# SHIELD_003.net
KiCad netlist of a schematic drawn in EAGLE
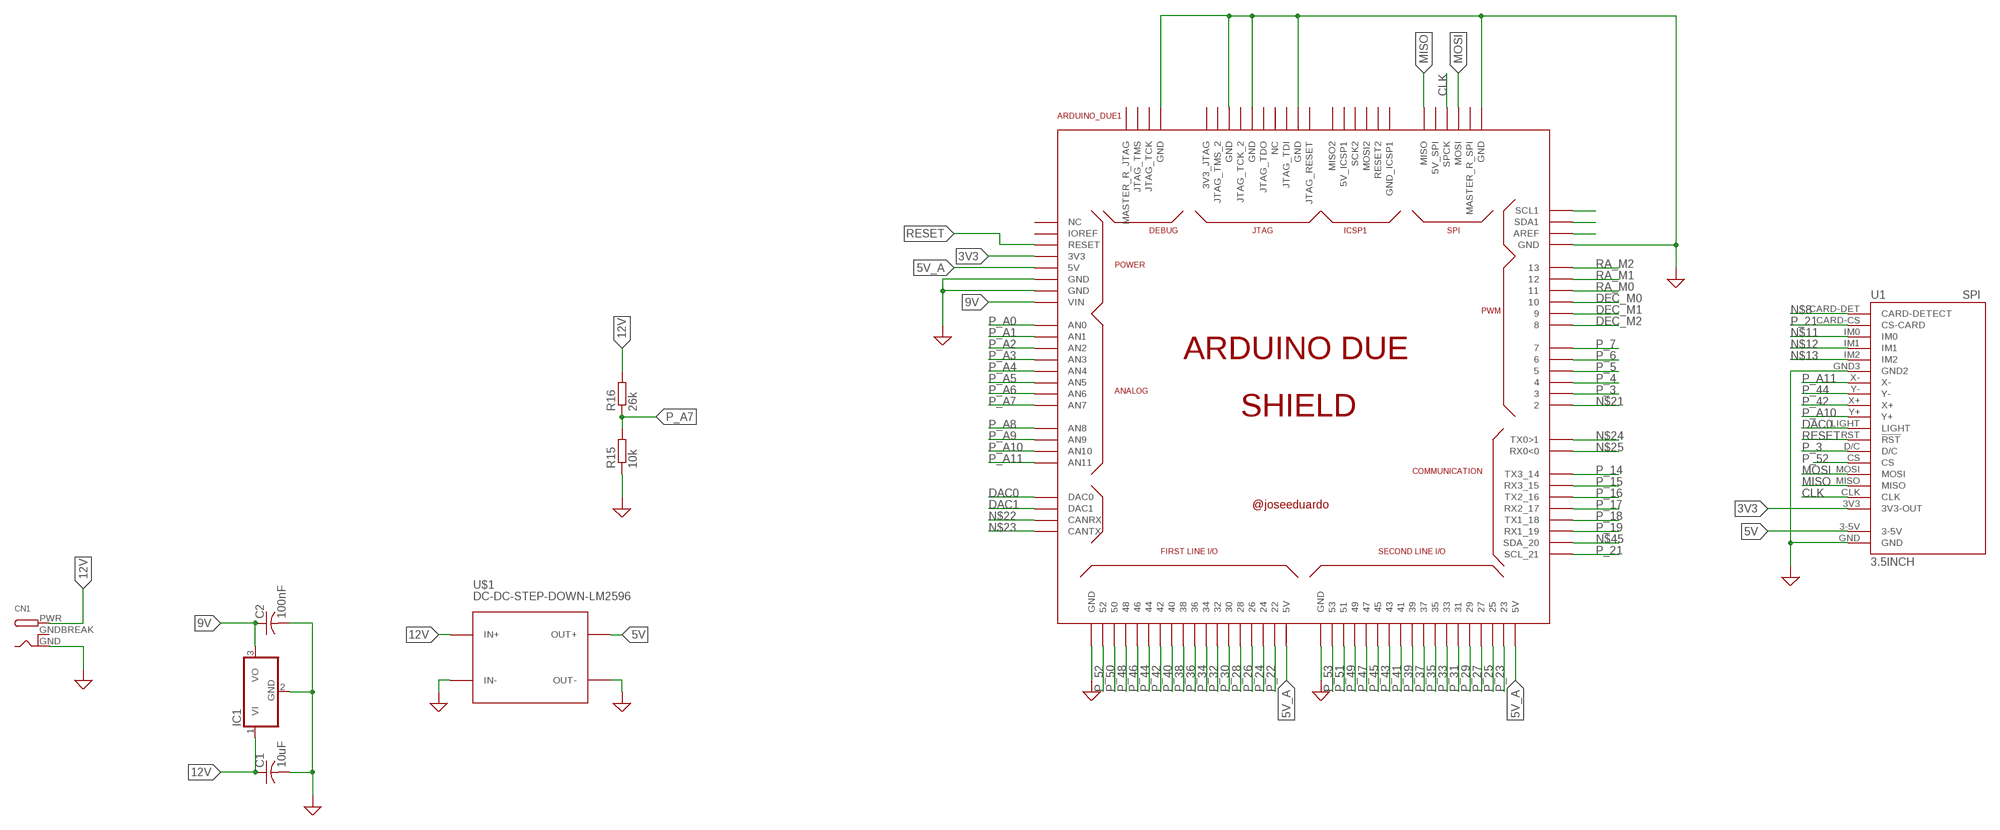
[diagram p0: schematic, sheet 1, part 1 of 3]
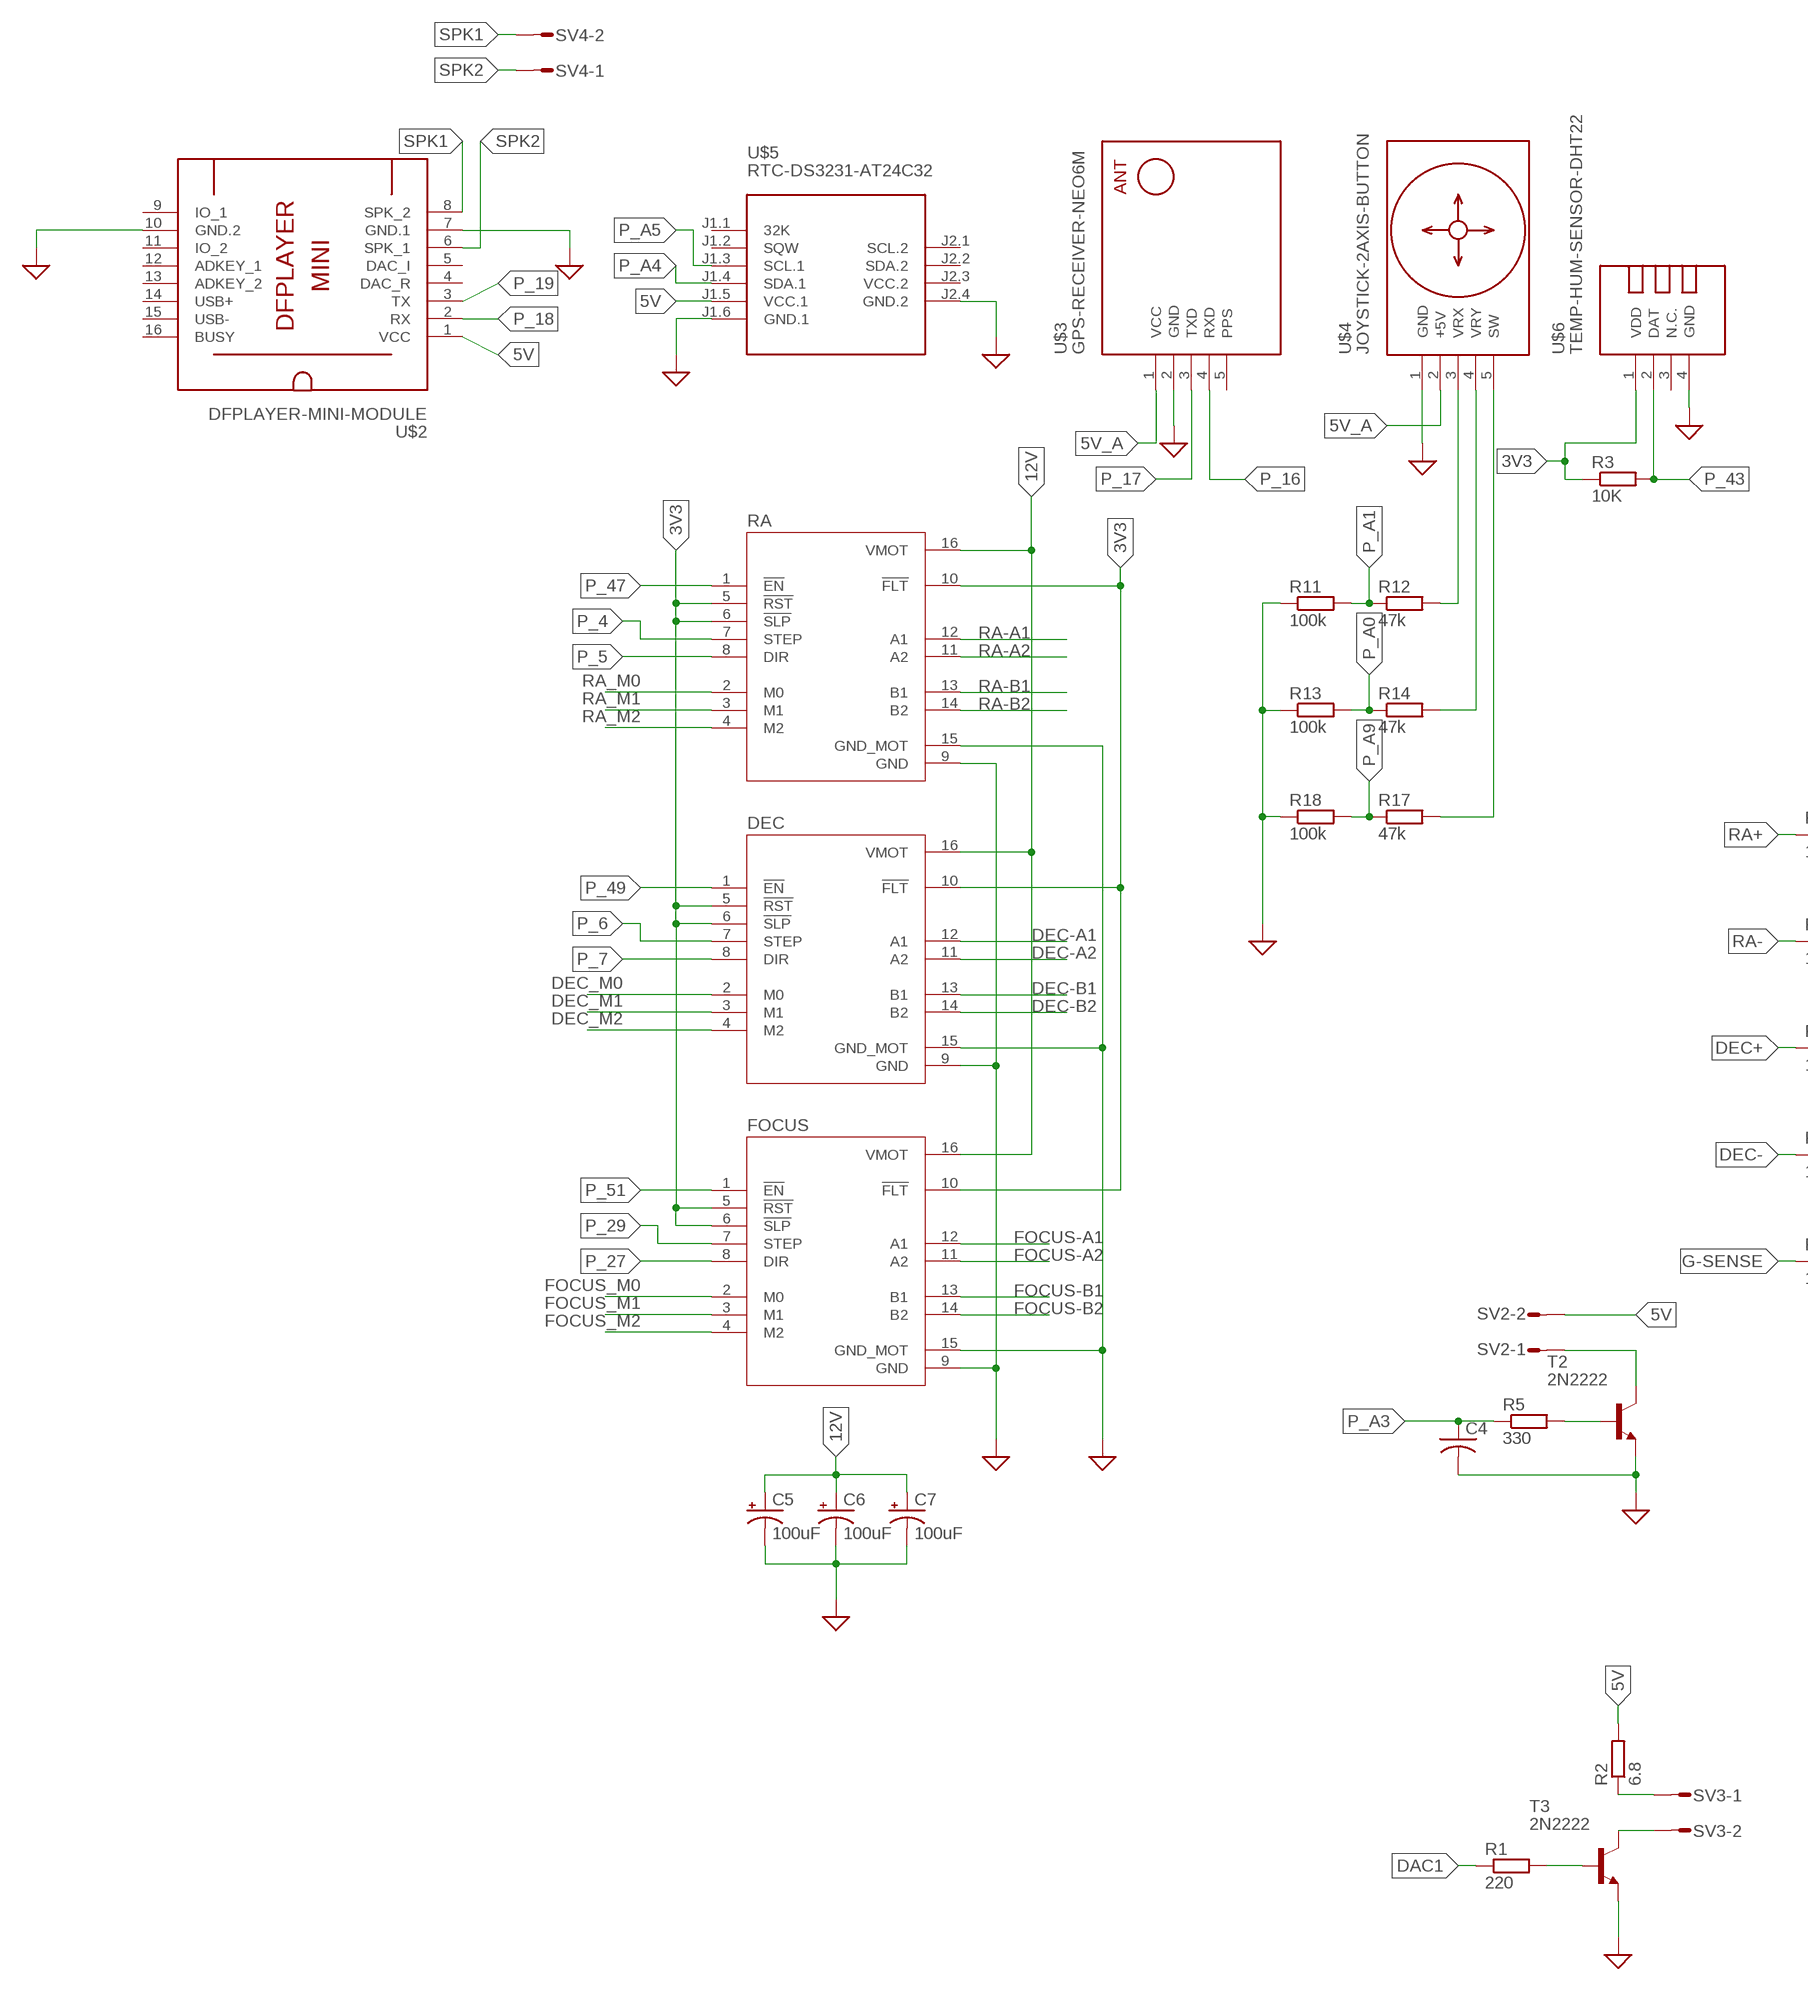
[diagram p1: schematic, sheet 1, part 2 of 3]
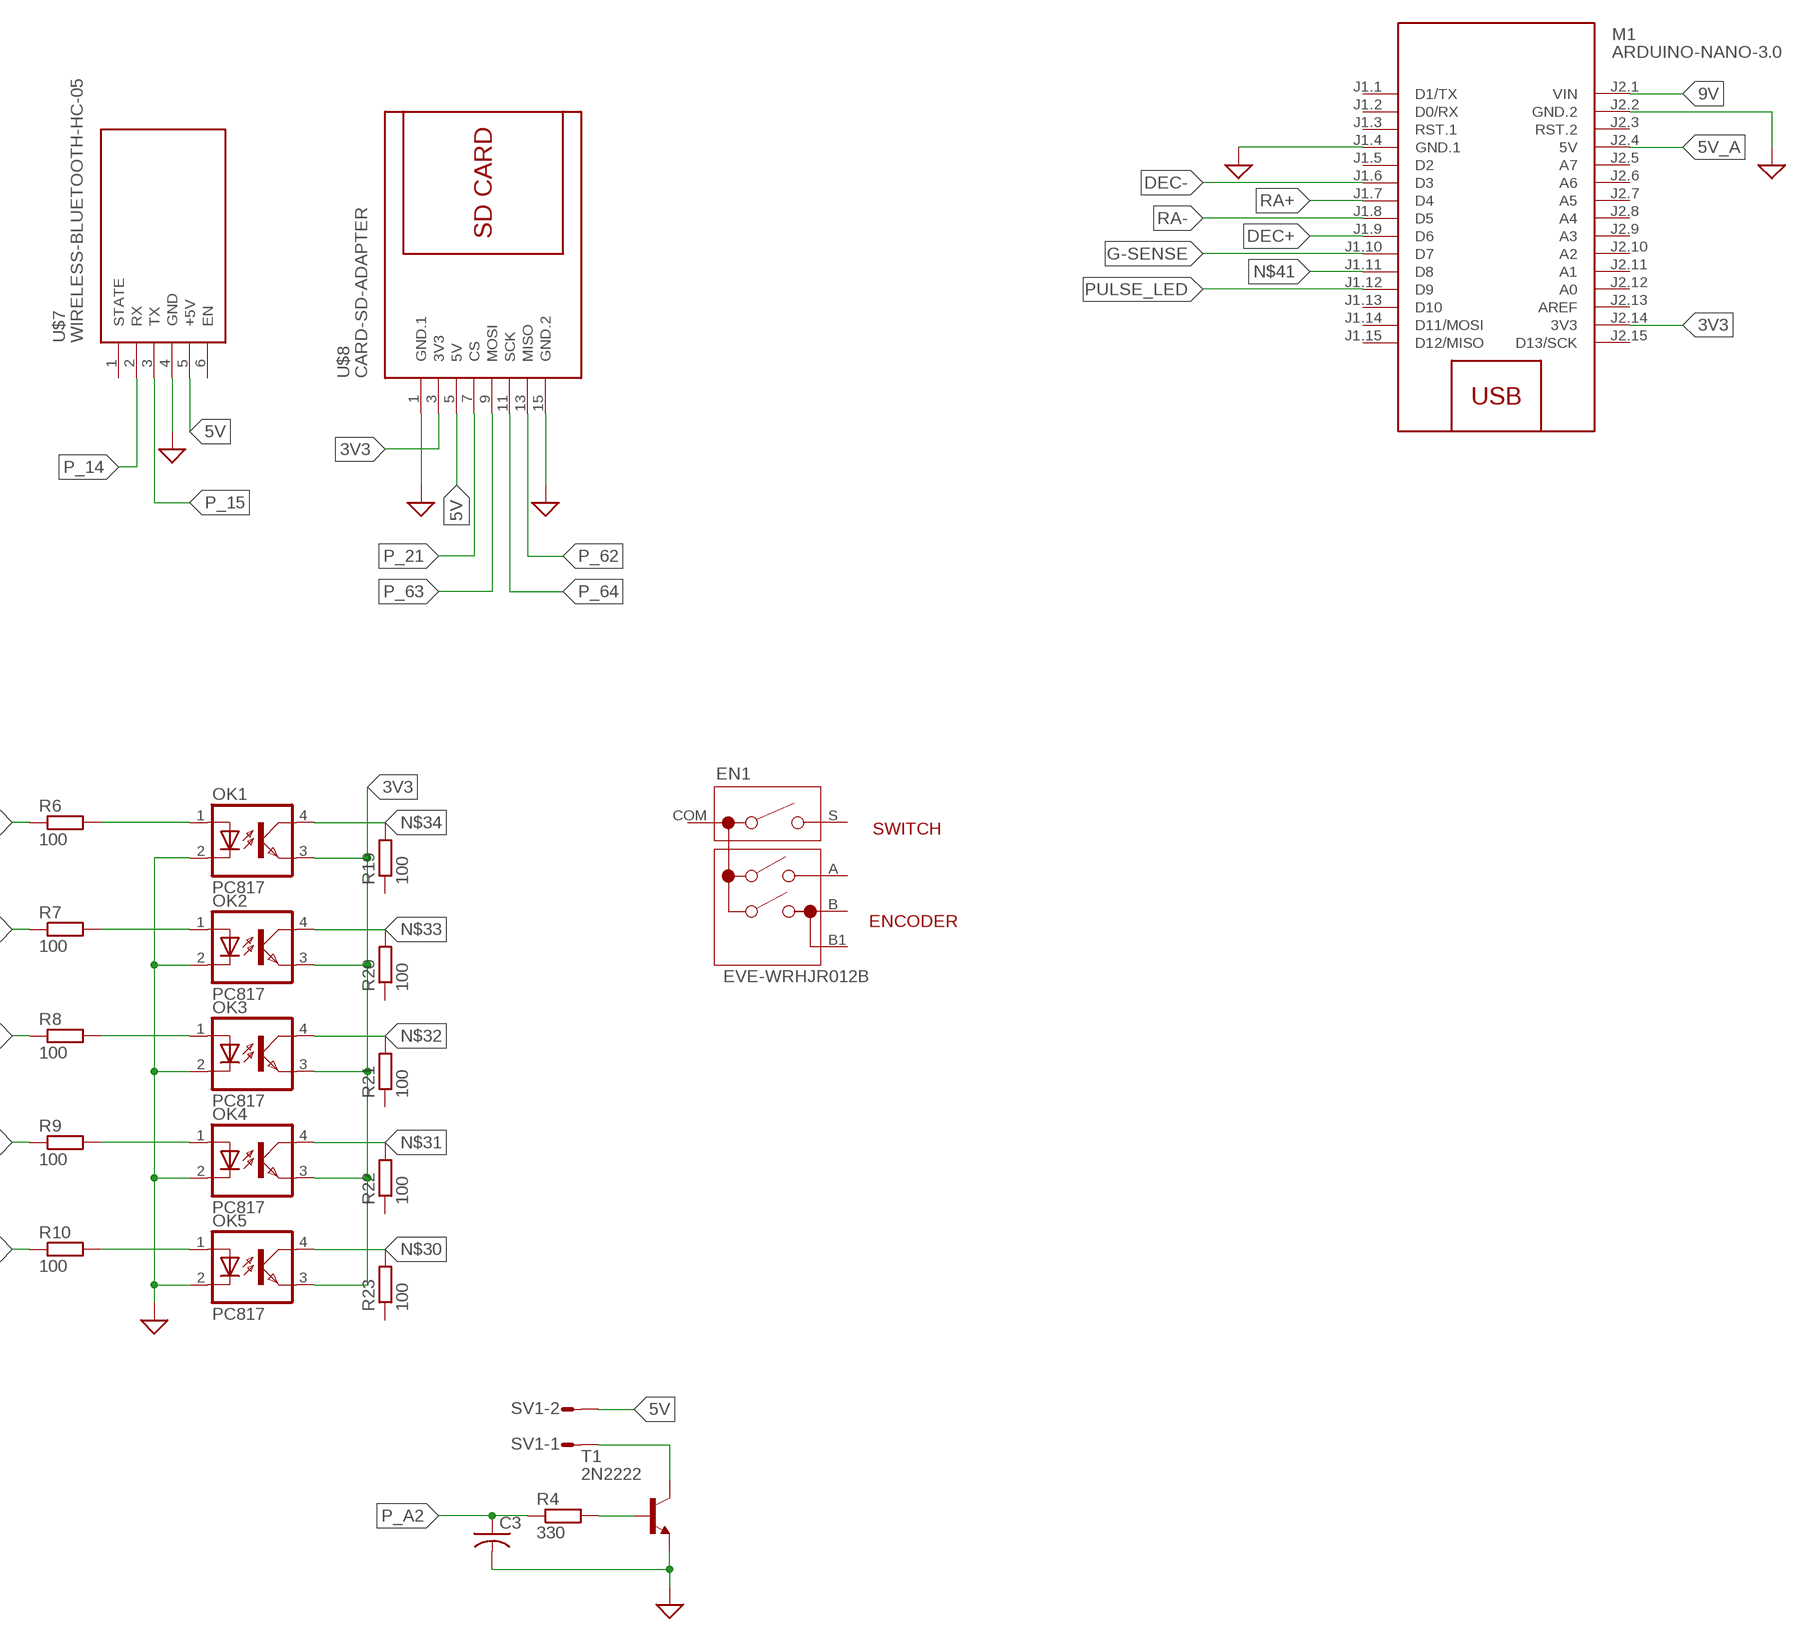
[diagram p2: schematic, sheet 1, part 3 of 3]

(export (version "E")
  (design (tool "Eeschema 10.0.6"))
  (components
    (comp (ref "ARDUINO_DUE1")
      (value "ARDUINO_DUE_SHIELD")
      (footprint "eagle-import:ARDUINO_DUE_SHIELD")
      (libsource (lib "eagle-import") (part "ARDUINO_DUE_SHIELD"))
    )
    (comp (ref "C1")
      (value "10uF")
      (footprint "eagle-import:C050-025X075")
      (libsource (lib "eagle-import") (part "C-US050-025X075"))
    )
    (comp (ref "C2")
      (value "100nF")
      (footprint "eagle-import:C050-025X075")
      (libsource (lib "eagle-import") (part "C-US050-025X075"))
    )
    (comp (ref "C3")
      (value "C-US050-025X075")
      (footprint "eagle-import:C050-025X075")
      (libsource (lib "eagle-import") (part "C-US050-025X075"))
    )
    (comp (ref "C4")
      (value "C-US050-025X075")
      (footprint "eagle-import:C050-025X075")
      (libsource (lib "eagle-import") (part "C-US050-025X075"))
    )
    (comp (ref "C5")
      (value "100uF")
      (footprint "eagle-import:E2-4")
      (libsource (lib "eagle-import") (part "CAPACITOR-PE2-4"))
    )
    (comp (ref "C6")
      (value "100uF")
      (footprint "eagle-import:E2-4")
      (libsource (lib "eagle-import") (part "CAPACITOR-PE2-4"))
    )
    (comp (ref "C7")
      (value "100uF")
      (footprint "eagle-import:E2-4")
      (libsource (lib "eagle-import") (part "CAPACITOR-PE2-4"))
    )
    (comp (ref "CN1")
      (value "DCBARRELPTH")
      (footprint "eagle-import:DCJACK_2MM_PTH")
      (libsource (lib "eagle-import") (part "DCBARRELPTH"))
    )
    (comp (ref "DEC")
      (value "DRV8825_STEPPER_MOTOR_DRIVER_CARRIER")
      (footprint "eagle-import:IC_DRV8825_STEPPER_MOTOR_DRIVER_CARRIER")
      (fields (field (name "MF") "Pololu") (field (name "MP") "DRV8825 STEPPER MOTOR DRIVER CARRIER"))
      (libsource (lib "eagle-import") (part "DRV8825_STEPPER_MOTOR_DRIVER_CARRIER"))
    )
    (comp (ref "EN1")
      (value "EVE-WRHJR012B")
      (footprint "eagle-import:EVE-WRHJR012B")
      (fields
        (field (name "DIGIKEY_PARTNO") "P15917-ND")
        (field (name "MANUFACTURER") "Panasonic Electronic Components")
        (field (name "CREATED_BY") "PCBLayout.com")
      )
      (libsource (lib "eagle-import") (part "EVE-WRHJR012B"))
    )
    (comp (ref "FOCUS")
      (value "DRV8825_STEPPER_MOTOR_DRIVER_CARRIER")
      (footprint "eagle-import:IC_DRV8825_STEPPER_MOTOR_DRIVER_CARRIER")
      (fields (field (name "MF") "Pololu") (field (name "MP") "DRV8825 STEPPER MOTOR DRIVER CARRIER"))
      (libsource (lib "eagle-import") (part "DRV8825_STEPPER_MOTOR_DRIVER_CARRIER"))
    )
    (comp (ref "IC1")
      (value "7805T")
      (footprint "eagle-import:TO220H")
      (libsource (lib "eagle-import") (part "78T05"))
    )
    (comp (ref "M1")
      (value "ARDUINO-NANO-3.0")
      (footprint "eagle-import:ARDUINO-NANO-3.0")
      (libsource (lib "eagle-import") (part "ARDUINO-NANO-3.0"))
    )
    (comp (ref "OK1")
      (value "PC817")
      (footprint "eagle-import:DIL04")
      (libsource (lib "eagle-import") (part "PC817"))
    )
    (comp (ref "OK2")
      (value "PC817")
      (footprint "eagle-import:DIL04")
      (libsource (lib "eagle-import") (part "PC817"))
    )
    (comp (ref "OK3")
      (value "PC817")
      (footprint "eagle-import:DIL04")
      (libsource (lib "eagle-import") (part "PC817"))
    )
    (comp (ref "OK4")
      (value "PC817")
      (footprint "eagle-import:DIL04")
      (libsource (lib "eagle-import") (part "PC817"))
    )
    (comp (ref "OK5")
      (value "PC817")
      (footprint "eagle-import:DIL04")
      (libsource (lib "eagle-import") (part "PC817"))
    )
    (comp (ref "R1")
      (value "220")
      (footprint "eagle-import:0207_10")
      (libsource (lib "eagle-import") (part "R0207/10"))
    )
    (comp (ref "R2")
      (value "6.8")
      (footprint "eagle-import:0207_10")
      (libsource (lib "eagle-import") (part "R0207/10"))
    )
    (comp (ref "R3")
      (value "10K")
      (footprint "eagle-import:0207_10")
      (libsource (lib "eagle-import") (part "R0207/10"))
    )
    (comp (ref "R4")
      (value "330")
      (footprint "eagle-import:0207_10")
      (libsource (lib "eagle-import") (part "R0207/10"))
    )
    (comp (ref "R5")
      (value "330")
      (footprint "eagle-import:0207_10")
      (libsource (lib "eagle-import") (part "R0207/10"))
    )
    (comp (ref "R6")
      (value "100")
      (footprint "eagle-import:0207_10")
      (libsource (lib "eagle-import") (part "R0207/10"))
    )
    (comp (ref "R7")
      (value "100")
      (footprint "eagle-import:0207_10")
      (libsource (lib "eagle-import") (part "R0207/10"))
    )
    (comp (ref "R8")
      (value "100")
      (footprint "eagle-import:0207_10")
      (libsource (lib "eagle-import") (part "R0207/10"))
    )
    (comp (ref "R9")
      (value "100")
      (footprint "eagle-import:0207_10")
      (libsource (lib "eagle-import") (part "R0207/10"))
    )
    (comp (ref "R10")
      (value "100")
      (footprint "eagle-import:0207_10")
      (libsource (lib "eagle-import") (part "R0207/10"))
    )
    (comp (ref "R11")
      (value "100k")
      (footprint "eagle-import:0207_10")
      (libsource (lib "eagle-import") (part "R0207/10"))
    )
    (comp (ref "R12")
      (value "47k")
      (footprint "eagle-import:0207_10")
      (libsource (lib "eagle-import") (part "R0207/10"))
    )
    (comp (ref "R13")
      (value "100k")
      (footprint "eagle-import:0207_10")
      (libsource (lib "eagle-import") (part "R0207/10"))
    )
    (comp (ref "R14")
      (value "47k")
      (footprint "eagle-import:0207_10")
      (libsource (lib "eagle-import") (part "R0207/10"))
    )
    (comp (ref "R15")
      (value "10k")
      (footprint "eagle-import:0207_10")
      (libsource (lib "eagle-import") (part "R0207/10"))
    )
    (comp (ref "R16")
      (value "26k")
      (footprint "eagle-import:0207_10")
      (libsource (lib "eagle-import") (part "R0207/10"))
    )
    (comp (ref "R17")
      (value "47k")
      (footprint "eagle-import:0207_10")
      (libsource (lib "eagle-import") (part "R0207/10"))
    )
    (comp (ref "R18")
      (value "100k")
      (footprint "eagle-import:0207_10")
      (libsource (lib "eagle-import") (part "R0207/10"))
    )
    (comp (ref "R19")
      (value "100")
      (footprint "eagle-import:0207_10")
      (libsource (lib "eagle-import") (part "R0207/10"))
    )
    (comp (ref "R20")
      (value "100")
      (footprint "eagle-import:0207_10")
      (libsource (lib "eagle-import") (part "R0207/10"))
    )
    (comp (ref "R21")
      (value "100")
      (footprint "eagle-import:0207_10")
      (libsource (lib "eagle-import") (part "R0207/10"))
    )
    (comp (ref "R22")
      (value "100")
      (footprint "eagle-import:0207_10")
      (libsource (lib "eagle-import") (part "R0207/10"))
    )
    (comp (ref "R23")
      (value "100")
      (footprint "eagle-import:0207_10")
      (libsource (lib "eagle-import") (part "R0207/10"))
    )
    (comp (ref "RA")
      (value "DRV8825_STEPPER_MOTOR_DRIVER_CARRIER")
      (footprint "eagle-import:IC_DRV8825_STEPPER_MOTOR_DRIVER_CARRIER")
      (fields (field (name "MF") "Pololu") (field (name "MP") "DRV8825 STEPPER MOTOR DRIVER CARRIER"))
      (libsource (lib "eagle-import") (part "DRV8825_STEPPER_MOTOR_DRIVER_CARRIER"))
    )
    (comp (ref "SV1")
      (value "L02P")
      (footprint "eagle-import:L02P")
      (libsource (lib "eagle-import") (part "L02P"))
    )
    (comp (ref "SV2")
      (value "L02P")
      (footprint "eagle-import:L02P")
      (libsource (lib "eagle-import") (part "L02P"))
    )
    (comp (ref "SV3")
      (value "L02P")
      (footprint "eagle-import:L02P")
      (libsource (lib "eagle-import") (part "L02P"))
    )
    (comp (ref "SV4")
      (value "L02P")
      (footprint "eagle-import:L02P")
      (libsource (lib "eagle-import") (part "L02P"))
    )
    (comp (ref "T1")
      (value "2N2222")
      (footprint "eagle-import:TO92-EBC-OVAL")
      (libsource (lib "eagle-import") (part "2N2222"))
    )
    (comp (ref "T2")
      (value "2N2222")
      (footprint "eagle-import:TO92-EBC-OVAL")
      (libsource (lib "eagle-import") (part "2N2222"))
    )
    (comp (ref "T3")
      (value "2N2222")
      (footprint "eagle-import:TO92-EBC-OVAL")
      (libsource (lib "eagle-import") (part "2N2222"))
    )
    (comp (ref "U$1")
      (value "DC-DC-STEP-DOWN-LM2596")
      (footprint "eagle-import:DC-DC-STEP-DOWN-LM2596")
      (libsource (lib "eagle-import") (part "DC-DC-STEP-DOWN-LM2596"))
    )
    (comp (ref "U$2")
      (value "DFPLAYER-MINI-MODULE")
      (footprint "eagle-import:DFPLAYER-MINI-MODULE")
      (libsource (lib "eagle-import") (part "DFPLAYER-MINI-MODULE"))
    )
    (comp (ref "U$3")
      (value "GPS-RECEIVER-NEO6M")
      (footprint "eagle-import:GPS-RECEIVER-NEO6M")
      (libsource (lib "eagle-import") (part "GPS-RECEIVER-NEO6M"))
    )
    (comp (ref "U$4")
      (value "JOYSTICK-2AXIS-BUTTON")
      (footprint "eagle-import:JOYSTICK-2AXIS-BUTTON")
      (libsource (lib "eagle-import") (part "JOYSTICK-2AXIS-BUTTON"))
    )
    (comp (ref "U$5")
      (value "RTC-DS3231-AT24C32")
      (footprint "eagle-import:RTC-DS3231-AT24C32")
      (libsource (lib "eagle-import") (part "RTC-DS3231-AT24C32"))
    )
    (comp (ref "U$6")
      (value "TEMP-HUM-SENSOR-DHT22")
      (footprint "eagle-import:TEMP-HUM-SENSOR-DHT22")
      (libsource (lib "eagle-import") (part "TEMP-HUM-SENSOR-DHT22"))
    )
    (comp (ref "U$7")
      (value "WIRELESS-BLUETOOTH-HC-05")
      (footprint "eagle-import:WIRELESS-BLUETOOTH-HC-05")
      (libsource (lib "eagle-import") (part "WIRELESS-BLUETOOTH-HC-05"))
    )
    (comp (ref "U$8")
      (value "CARD-SD-ADAPTER")
      (footprint "eagle-import:CARD-SD-ADAPTER")
      (libsource (lib "eagle-import") (part "CARD-SD-ADAPTER"))
    )
    (comp (ref "U1")
      (value "3.5INCH")
      (footprint "eagle-import:3.5INCH")
      (fields (field (name "MF") "Pololu") (field (name "MP") "DRV8825 STEPPER MOTOR DRIVER CARRIER"))
      (libsource (lib "eagle-import") (part "3.5INCH"))
    )
  )
  (nets
    (net (code "1") (name "/CLK") (class "Default")
      (node (ref "ARDUINO_DUE1") (pin "SPCK") (pinfunction "SPCK_SPCK") (pintype "bidirectional"))
      (node (ref "U1") (pin "CLK") (pinfunction "CLK_CLK") (pintype "input"))
    )
    (net (code "2") (name "/DAC0") (class "Default")
      (node (ref "ARDUINO_DUE1") (pin "DAC0") (pinfunction "DAC0_DAC0") (pintype "bidirectional"))
      (node (ref "U1") (pin "LIGHT") (pinfunction "LIGHT_LIGHT") (pintype "input"))
    )
    (net (code "3") (name "/DEC-A1") (class "Default")
      (node (ref "DEC") (pin "12") (pinfunction "A1_12") (pintype "output"))
    )
    (net (code "4") (name "/DEC-A2") (class "Default")
      (node (ref "DEC") (pin "11") (pinfunction "A2_11") (pintype "output"))
    )
    (net (code "5") (name "/DEC-B1") (class "Default")
      (node (ref "DEC") (pin "13") (pinfunction "B1_13") (pintype "output"))
    )
    (net (code "6") (name "/DEC-B2") (class "Default")
      (node (ref "DEC") (pin "14") (pinfunction "B2_14") (pintype "output"))
    )
    (net (code "7") (name "/DEC_M0") (class "Default")
      (node (ref "ARDUINO_DUE1") (pin "10") (pinfunction "10_10") (pintype "bidirectional"))
      (node (ref "DEC") (pin "2") (pinfunction "M0_2") (pintype "input"))
    )
    (net (code "8") (name "/DEC_M1") (class "Default")
      (node (ref "ARDUINO_DUE1") (pin "9") (pinfunction "9_9") (pintype "bidirectional"))
      (node (ref "DEC") (pin "3") (pinfunction "M1_3") (pintype "input"))
    )
    (net (code "9") (name "/DEC_M2") (class "Default")
      (node (ref "ARDUINO_DUE1") (pin "8") (pinfunction "8_8") (pintype "bidirectional"))
      (node (ref "DEC") (pin "4") (pinfunction "M2_4") (pintype "input"))
    )
    (net (code "10") (name "/FOCUS-A1") (class "Default")
      (node (ref "FOCUS") (pin "12") (pinfunction "A1_12") (pintype "output"))
    )
    (net (code "11") (name "/FOCUS-A2") (class "Default")
      (node (ref "FOCUS") (pin "11") (pinfunction "A2_11") (pintype "output"))
    )
    (net (code "12") (name "/FOCUS-B1") (class "Default")
      (node (ref "FOCUS") (pin "13") (pinfunction "B1_13") (pintype "output"))
    )
    (net (code "13") (name "/FOCUS-B2") (class "Default")
      (node (ref "FOCUS") (pin "14") (pinfunction "B2_14") (pintype "output"))
    )
    (net (code "14") (name "/FOCUS_M0") (class "Default")
      (node (ref "FOCUS") (pin "2") (pinfunction "M0_2") (pintype "input"))
    )
    (net (code "15") (name "/FOCUS_M1") (class "Default")
      (node (ref "FOCUS") (pin "3") (pinfunction "M1_3") (pintype "input"))
    )
    (net (code "16") (name "/FOCUS_M2") (class "Default")
      (node (ref "FOCUS") (pin "4") (pinfunction "M2_4") (pintype "input"))
    )
    (net (code "17") (name "/GNDBREAK") (class "Default")
      (node (ref "CN1") (pin "GNDBREAK") (pinfunction "GNDBREAK_GNDBREAK") (pintype "power_in"))
    )
    (net (code "18") (name "/N$8") (class "Default")
      (node (ref "U1") (pin "CARD-DET") (pinfunction "CARD-DETECT_CARD-DET") (pintype "input"))
    )
    (net (code "19") (name "/N$11") (class "Default")
      (node (ref "U1") (pin "IM0") (pinfunction "IM0_IM0") (pintype "input"))
    )
    (net (code "20") (name "/N$12") (class "Default")
      (node (ref "U1") (pin "IM1") (pinfunction "IM1_IM1") (pintype "input"))
    )
    (net (code "21") (name "/N$13") (class "Default")
      (node (ref "U1") (pin "IM2") (pinfunction "IM2_IM2") (pintype "input"))
    )
    (net (code "22") (name "/N$21") (class "Default")
      (node (ref "ARDUINO_DUE1") (pin "2") (pinfunction "2_2") (pintype "bidirectional"))
    )
    (net (code "23") (name "/N$22") (class "Default")
      (node (ref "ARDUINO_DUE1") (pin "CANRX") (pinfunction "CANRX_CANRX") (pintype "bidirectional"))
    )
    (net (code "24") (name "/N$23") (class "Default")
      (node (ref "ARDUINO_DUE1") (pin "CANTX") (pinfunction "CANTX_CANTX") (pintype "bidirectional"))
    )
    (net (code "25") (name "/N$24") (class "Default")
      (node (ref "ARDUINO_DUE1") (pin "1") (pinfunction "TX0>1_1") (pintype "bidirectional"))
    )
    (net (code "26") (name "/N$25") (class "Default")
      (node (ref "ARDUINO_DUE1") (pin "0") (pinfunction "RX0<0_0") (pintype "bidirectional"))
    )
    (net (code "27") (name "/N$45") (class "Default")
      (node (ref "ARDUINO_DUE1") (pin "20") (pinfunction "SDA_20_20") (pintype "bidirectional"))
    )
    (net (code "28") (name "/PPS") (class "Default")
      (node (ref "U$3") (pin "5") (pinfunction "PPS_5") (pintype "power_in"))
    )
    (net (code "29") (name "/P_3") (class "Default")
      (node (ref "ARDUINO_DUE1") (pin "3") (pinfunction "3_3") (pintype "bidirectional"))
      (node (ref "U1") (pin "D/C") (pinfunction "D/C_D/C") (pintype "input"))
    )
    (net (code "30") (name "/P_22") (class "Default")
      (node (ref "ARDUINO_DUE1") (pin "22") (pinfunction "22_22") (pintype "bidirectional"))
    )
    (net (code "31") (name "/P_23") (class "Default")
      (node (ref "ARDUINO_DUE1") (pin "23") (pinfunction "23_23") (pintype "bidirectional"))
    )
    (net (code "32") (name "/P_24") (class "Default")
      (node (ref "ARDUINO_DUE1") (pin "24") (pinfunction "24_24") (pintype "bidirectional"))
    )
    (net (code "33") (name "/P_25") (class "Default")
      (node (ref "ARDUINO_DUE1") (pin "25") (pinfunction "25_25") (pintype "bidirectional"))
    )
    (net (code "34") (name "/P_26") (class "Default")
      (node (ref "ARDUINO_DUE1") (pin "26") (pinfunction "26_26") (pintype "bidirectional"))
    )
    (net (code "35") (name "/P_28") (class "Default")
      (node (ref "ARDUINO_DUE1") (pin "28") (pinfunction "28_28") (pintype "bidirectional"))
    )
    (net (code "36") (name "/P_30") (class "Default")
      (node (ref "ARDUINO_DUE1") (pin "30") (pinfunction "30_30") (pintype "bidirectional"))
    )
    (net (code "37") (name "/P_31") (class "Default")
      (node (ref "ARDUINO_DUE1") (pin "31") (pinfunction "31_31") (pintype "bidirectional"))
    )
    (net (code "38") (name "/P_32") (class "Default")
      (node (ref "ARDUINO_DUE1") (pin "32") (pinfunction "32_32") (pintype "bidirectional"))
    )
    (net (code "39") (name "/P_33") (class "Default")
      (node (ref "ARDUINO_DUE1") (pin "33") (pinfunction "33_33") (pintype "bidirectional"))
    )
    (net (code "40") (name "/P_34") (class "Default")
      (node (ref "ARDUINO_DUE1") (pin "34") (pinfunction "34_34") (pintype "bidirectional"))
    )
    (net (code "41") (name "/P_35") (class "Default")
      (node (ref "ARDUINO_DUE1") (pin "35") (pinfunction "35_35") (pintype "bidirectional"))
    )
    (net (code "42") (name "/P_36") (class "Default")
      (node (ref "ARDUINO_DUE1") (pin "36") (pinfunction "36_36") (pintype "bidirectional"))
    )
    (net (code "43") (name "/P_37") (class "Default")
      (node (ref "ARDUINO_DUE1") (pin "37") (pinfunction "37_37") (pintype "bidirectional"))
    )
    (net (code "44") (name "/P_38") (class "Default")
      (node (ref "ARDUINO_DUE1") (pin "38") (pinfunction "38_38") (pintype "bidirectional"))
    )
    (net (code "45") (name "/P_39") (class "Default")
      (node (ref "ARDUINO_DUE1") (pin "39") (pinfunction "39_39") (pintype "bidirectional"))
    )
    (net (code "46") (name "/P_40") (class "Default")
      (node (ref "ARDUINO_DUE1") (pin "40") (pinfunction "40_40") (pintype "bidirectional"))
    )
    (net (code "47") (name "/P_41") (class "Default")
      (node (ref "ARDUINO_DUE1") (pin "41") (pinfunction "41_41") (pintype "bidirectional"))
    )
    (net (code "48") (name "/P_42") (class "Default")
      (node (ref "ARDUINO_DUE1") (pin "42") (pinfunction "42_42") (pintype "bidirectional"))
      (node (ref "U1") (pin "X+") (pinfunction "X+_X+") (pintype "input"))
    )
    (net (code "49") (name "/P_44") (class "Default")
      (node (ref "ARDUINO_DUE1") (pin "44") (pinfunction "44_44") (pintype "bidirectional"))
      (node (ref "U1") (pin "Y-") (pinfunction "Y-_Y-") (pintype "input"))
    )
    (net (code "50") (name "/P_45") (class "Default")
      (node (ref "ARDUINO_DUE1") (pin "45") (pinfunction "45_45") (pintype "bidirectional"))
    )
    (net (code "51") (name "/P_46") (class "Default")
      (node (ref "ARDUINO_DUE1") (pin "46") (pinfunction "46_46") (pintype "bidirectional"))
    )
    (net (code "52") (name "/P_48") (class "Default")
      (node (ref "ARDUINO_DUE1") (pin "48") (pinfunction "48_48") (pintype "bidirectional"))
    )
    (net (code "53") (name "/P_50") (class "Default")
      (node (ref "ARDUINO_DUE1") (pin "50") (pinfunction "50_50") (pintype "bidirectional"))
    )
    (net (code "54") (name "/P_52") (class "Default")
      (node (ref "ARDUINO_DUE1") (pin "52") (pinfunction "52_52") (pintype "bidirectional"))
      (node (ref "U1") (pin "CS") (pinfunction "CS_CS") (pintype "input"))
    )
    (net (code "55") (name "/P_53") (class "Default")
      (node (ref "ARDUINO_DUE1") (pin "53") (pinfunction "53_53") (pintype "bidirectional"))
    )
    (net (code "56") (name "/P_A6") (class "Default")
      (node (ref "ARDUINO_DUE1") (pin "A6") (pinfunction "AN6_A6") (pintype "bidirectional"))
    )
    (net (code "57") (name "/P_A8") (class "Default")
      (node (ref "ARDUINO_DUE1") (pin "A8") (pinfunction "AN8_A8") (pintype "bidirectional"))
    )
    (net (code "58") (name "/P_A10") (class "Default")
      (node (ref "ARDUINO_DUE1") (pin "A10") (pinfunction "AN10_A10") (pintype "bidirectional"))
      (node (ref "U1") (pin "Y+") (pinfunction "Y+_Y+") (pintype "input"))
    )
    (net (code "59") (name "/P_A11") (class "Default")
      (node (ref "ARDUINO_DUE1") (pin "A11") (pinfunction "AN11_A11") (pintype "bidirectional"))
      (node (ref "U1") (pin "X-") (pinfunction "X-_X-") (pintype "input"))
    )
    (net (code "60") (name "/RA-A1") (class "Default")
      (node (ref "RA") (pin "12") (pinfunction "A1_12") (pintype "output"))
    )
    (net (code "61") (name "/RA-A2") (class "Default")
      (node (ref "RA") (pin "11") (pinfunction "A2_11") (pintype "output"))
    )
    (net (code "62") (name "/RA-B1") (class "Default")
      (node (ref "RA") (pin "13") (pinfunction "B1_13") (pintype "output"))
    )
    (net (code "63") (name "/RA-B2") (class "Default")
      (node (ref "RA") (pin "14") (pinfunction "B2_14") (pintype "output"))
    )
    (net (code "64") (name "/RA_M0") (class "Default")
      (node (ref "ARDUINO_DUE1") (pin "11") (pinfunction "11_11") (pintype "bidirectional"))
      (node (ref "RA") (pin "2") (pinfunction "M0_2") (pintype "input"))
    )
    (net (code "65") (name "/RA_M1") (class "Default")
      (node (ref "ARDUINO_DUE1") (pin "12") (pinfunction "12_12") (pintype "bidirectional"))
      (node (ref "RA") (pin "3") (pinfunction "M1_3") (pintype "input"))
    )
    (net (code "66") (name "/RA_M2") (class "Default")
      (node (ref "ARDUINO_DUE1") (pin "13") (pinfunction "13_13") (pintype "bidirectional"))
      (node (ref "RA") (pin "4") (pinfunction "M2_4") (pintype "input"))
    )
    (net (code "67") (name "/VCC.2") (class "Default")
      (node (ref "U$5") (pin "J2.3") (pinfunction "VCC.2_J2.3") (pintype "power_in"))
    )
    (net (code "68") (name "3V3") (class "Default")
      (node (ref "ARDUINO_DUE1") (pin "3V3") (pinfunction "3V3_3V3") (pintype "bidirectional"))
      (node (ref "DEC") (pin "10") (pinfunction "~{FLT}_10") (pintype "output"))
      (node (ref "DEC") (pin "5") (pinfunction "~{RST}_5") (pintype "input"))
      (node (ref "DEC") (pin "6") (pinfunction "~{SLP}_6") (pintype "input"))
      (node (ref "FOCUS") (pin "10") (pinfunction "~{FLT}_10") (pintype "output"))
      (node (ref "FOCUS") (pin "5") (pinfunction "~{RST}_5") (pintype "input"))
      (node (ref "FOCUS") (pin "6") (pinfunction "~{SLP}_6") (pintype "input"))
      (node (ref "M1") (pin "J2.14") (pinfunction "3V3_J2.14") (pintype "power_in"))
      (node (ref "OK1") (pin "3") (pinfunction "EMIT_3") (pintype "passive"))
      (node (ref "OK2") (pin "3") (pinfunction "EMIT_3") (pintype "passive"))
      (node (ref "OK3") (pin "3") (pinfunction "EMIT_3") (pintype "passive"))
      (node (ref "OK4") (pin "3") (pinfunction "EMIT_3") (pintype "passive"))
      (node (ref "OK5") (pin "3") (pinfunction "EMIT_3") (pintype "passive"))
      (node (ref "R3") (pin "1") (pinfunction "1_1") (pintype "passive"))
      (node (ref "RA") (pin "10") (pinfunction "~{FLT}_10") (pintype "output"))
      (node (ref "RA") (pin "5") (pinfunction "~{RST}_5") (pintype "input"))
      (node (ref "RA") (pin "6") (pinfunction "~{SLP}_6") (pintype "input"))
      (node (ref "U$6") (pin "1") (pinfunction "VDD_1") (pintype "power_in"))
      (node (ref "U$8") (pin "3") (pinfunction "3V3_3") (pintype "power_in"))
      (node (ref "U1") (pin "3V3") (pinfunction "3V3-OUT_3V3") (pintype "output"))
    )
    (net (code "69") (name "5V") (class "Default")
      (node (ref "R2") (pin "2") (pinfunction "2_2") (pintype "passive"))
      (node (ref "SV1") (pin "2") (pinfunction "S_2") (pintype "passive"))
      (node (ref "SV2") (pin "2") (pinfunction "S_2") (pintype "passive"))
      (node (ref "U$1") (pin "OUT+") (pinfunction "OUT+_OUT+") (pintype "bidirectional"))
      (node (ref "U$2") (pin "1") (pinfunction "VCC_1") (pintype "power_in"))
      (node (ref "U$5") (pin "J1.5") (pinfunction "VCC.1_J1.5") (pintype "power_in"))
      (node (ref "U$7") (pin "5") (pinfunction "+5V_5") (pintype "power_in"))
      (node (ref "U$8") (pin "5") (pinfunction "5V_5") (pintype "power_in"))
      (node (ref "U1") (pin "3-5V") (pinfunction "3-5V_3-5V") (pintype "power_in"))
    )
    (net (code "70") (name "5V_A") (class "Default")
      (node (ref "ARDUINO_DUE1") (pin "5V0") (pinfunction "5V_5V0") (pintype "bidirectional"))
      (node (ref "ARDUINO_DUE1") (pin "5V0_1") (pinfunction "5V_5V0_1") (pintype "bidirectional"))
      (node (ref "ARDUINO_DUE1") (pin "5V0_2") (pinfunction "5V_5V0_2") (pintype "bidirectional"))
      (node (ref "M1") (pin "J2.4") (pinfunction "5V_J2.4") (pintype "power_in"))
      (node (ref "U$3") (pin "1") (pinfunction "VCC_1") (pintype "bidirectional"))
      (node (ref "U$4") (pin "2") (pinfunction "+5V_2") (pintype "power_in"))
    )
    (net (code "71") (name "9V") (class "Default")
      (node (ref "ARDUINO_DUE1") (pin "VIN") (pinfunction "VIN_VIN") (pintype "bidirectional"))
      (node (ref "C2") (pin "1") (pinfunction "1_1") (pintype "passive"))
      (node (ref "IC1") (pin "3") (pinfunction "VO_3") (pintype "passive"))
      (node (ref "M1") (pin "J2.1") (pinfunction "VIN_J2.1") (pintype "power_in"))
    )
    (net (code "72") (name "12V") (class "Default")
      (node (ref "C1") (pin "1") (pinfunction "1_1") (pintype "passive"))
      (node (ref "C5") (pin "+") (pinfunction "+_+") (pintype "passive"))
      (node (ref "C6") (pin "+") (pinfunction "+_+") (pintype "passive"))
      (node (ref "C7") (pin "+") (pinfunction "+_+") (pintype "passive"))
      (node (ref "CN1") (pin "PWR") (pinfunction "PWR_PWR") (pintype "power_in"))
      (node (ref "DEC") (pin "16") (pinfunction "VMOT_16") (pintype "power_in"))
      (node (ref "FOCUS") (pin "16") (pinfunction "VMOT_16") (pintype "power_in"))
      (node (ref "IC1") (pin "1") (pinfunction "VI_1") (pintype "input"))
      (node (ref "R16") (pin "2") (pinfunction "2_2") (pintype "passive"))
      (node (ref "RA") (pin "16") (pinfunction "VMOT_16") (pintype "power_in"))
      (node (ref "U$1") (pin "IN+") (pinfunction "IN+_IN+") (pintype "bidirectional"))
    )
    (net (code "73") (name "DAC1") (class "Default")
      (node (ref "ARDUINO_DUE1") (pin "DAC1") (pinfunction "DAC1_DAC1") (pintype "bidirectional"))
      (node (ref "R1") (pin "1") (pinfunction "1_1") (pintype "passive"))
    )
    (net (code "74") (name "DEC+") (class "Default")
      (node (ref "M1") (pin "J1.9") (pinfunction "D6_J1.9") (pintype "bidirectional"))
      (node (ref "R8") (pin "1") (pinfunction "1_1") (pintype "passive"))
    )
    (net (code "75") (name "DEC-") (class "Default")
      (node (ref "M1") (pin "J1.6") (pinfunction "D3_J1.6") (pintype "bidirectional"))
      (node (ref "R9") (pin "1") (pinfunction "1_1") (pintype "passive"))
    )
    (net (code "76") (name "G-SENSE") (class "Default")
      (node (ref "M1") (pin "J1.10") (pinfunction "D7_J1.10") (pintype "bidirectional"))
      (node (ref "R10") (pin "1") (pinfunction "1_1") (pintype "passive"))
    )
    (net (code "77") (name "MISO") (class "Default")
      (node (ref "ARDUINO_DUE1") (pin "MISO") (pinfunction "MISO_MISO") (pintype "bidirectional"))
      (node (ref "U1") (pin "MISO") (pinfunction "MISO_MISO") (pintype "input"))
    )
    (net (code "78") (name "MOSI") (class "Default")
      (node (ref "ARDUINO_DUE1") (pin "MOSI") (pinfunction "MOSI_MOSI") (pintype "bidirectional"))
      (node (ref "U1") (pin "MOSI") (pinfunction "MOSI_MOSI") (pintype "input"))
    )
    (net (code "79") (name "N$30") (class "Default")
      (node (ref "OK5") (pin "4") (pinfunction "COL_4") (pintype "passive"))
      (node (ref "R23") (pin "2") (pinfunction "2_2") (pintype "passive"))
    )
    (net (code "80") (name "N$31") (class "Default")
      (node (ref "OK4") (pin "4") (pinfunction "COL_4") (pintype "passive"))
      (node (ref "R22") (pin "2") (pinfunction "2_2") (pintype "passive"))
    )
    (net (code "81") (name "N$32") (class "Default")
      (node (ref "OK3") (pin "4") (pinfunction "COL_4") (pintype "passive"))
      (node (ref "R21") (pin "2") (pinfunction "2_2") (pintype "passive"))
    )
    (net (code "82") (name "N$33") (class "Default")
      (node (ref "OK2") (pin "4") (pinfunction "COL_4") (pintype "passive"))
      (node (ref "R20") (pin "2") (pinfunction "2_2") (pintype "passive"))
    )
    (net (code "83") (name "N$34") (class "Default")
      (node (ref "OK1") (pin "4") (pinfunction "COL_4") (pintype "passive"))
      (node (ref "R19") (pin "2") (pinfunction "2_2") (pintype "passive"))
    )
    (net (code "84") (name "N$41") (class "Default")
      (node (ref "M1") (pin "J1.11") (pinfunction "D8_J1.11") (pintype "bidirectional"))
    )
    (net (code "85") (name "Net-(OK1-A)") (class "Default")
      (node (ref "OK1") (pin "1") (pinfunction "A_1") (pintype "passive"))
      (node (ref "R6") (pin "2") (pinfunction "2_2") (pintype "passive"))
    )
    (net (code "86") (name "Net-(OK2-A)") (class "Default")
      (node (ref "OK2") (pin "1") (pinfunction "A_1") (pintype "passive"))
      (node (ref "R7") (pin "2") (pinfunction "2_2") (pintype "passive"))
    )
    (net (code "87") (name "Net-(OK3-A)") (class "Default")
      (node (ref "OK3") (pin "1") (pinfunction "A_1") (pintype "passive"))
      (node (ref "R8") (pin "2") (pinfunction "2_2") (pintype "passive"))
    )
    (net (code "88") (name "Net-(OK4-A)") (class "Default")
      (node (ref "OK4") (pin "1") (pinfunction "A_1") (pintype "passive"))
      (node (ref "R9") (pin "2") (pinfunction "2_2") (pintype "passive"))
    )
    (net (code "89") (name "Net-(OK5-A)") (class "Default")
      (node (ref "OK5") (pin "1") (pinfunction "A_1") (pintype "passive"))
      (node (ref "R10") (pin "2") (pinfunction "2_2") (pintype "passive"))
    )
    (net (code "90") (name "Net-(R1-Pad2)") (class "Default")
      (node (ref "R1") (pin "2") (pinfunction "2_2") (pintype "passive"))
      (node (ref "T3") (pin "B") (pinfunction "B_B") (pintype "passive"))
    )
    (net (code "91") (name "Net-(R4-Pad2)") (class "Default")
      (node (ref "R4") (pin "2") (pinfunction "2_2") (pintype "passive"))
      (node (ref "T1") (pin "B") (pinfunction "B_B") (pintype "passive"))
    )
    (net (code "92") (name "Net-(R5-Pad2)") (class "Default")
      (node (ref "R5") (pin "2") (pinfunction "2_2") (pintype "passive"))
      (node (ref "T2") (pin "B") (pinfunction "B_B") (pintype "passive"))
    )
    (net (code "93") (name "Net-(SV1A-S)") (class "Default")
      (node (ref "SV1") (pin "1") (pinfunction "S_1") (pintype "passive"))
      (node (ref "T1") (pin "C") (pinfunction "C_C") (pintype "passive"))
    )
    (net (code "94") (name "Net-(SV2A-S)") (class "Default")
      (node (ref "SV2") (pin "1") (pinfunction "S_1") (pintype "passive"))
      (node (ref "T2") (pin "C") (pinfunction "C_C") (pintype "passive"))
    )
    (net (code "95") (name "Net-(SV3A-S)") (class "Default")
      (node (ref "R2") (pin "1") (pinfunction "1_1") (pintype "passive"))
      (node (ref "SV3") (pin "1") (pinfunction "S_1") (pintype "passive"))
    )
    (net (code "96") (name "Net-(SV3B-S)") (class "Default")
      (node (ref "SV3") (pin "2") (pinfunction "S_2") (pintype "passive"))
      (node (ref "T3") (pin "C") (pinfunction "C_C") (pintype "passive"))
    )
    (net (code "97") (name "Net-(U$4-SW)") (class "Default")
      (node (ref "R17") (pin "2") (pinfunction "2_2") (pintype "passive"))
      (node (ref "U$4") (pin "5") (pinfunction "SW_5") (pintype "passive"))
    )
    (net (code "98") (name "Net-(U$4-VRX)") (class "Default")
      (node (ref "R12") (pin "2") (pinfunction "2_2") (pintype "passive"))
      (node (ref "U$4") (pin "3") (pinfunction "VRX_3") (pintype "passive"))
    )
    (net (code "99") (name "Net-(U$4-VRY)") (class "Default")
      (node (ref "R14") (pin "2") (pinfunction "2_2") (pintype "passive"))
      (node (ref "U$4") (pin "4") (pinfunction "VRY_4") (pintype "passive"))
    )
    (net (code "100") (name "PULSE_LED") (class "Default")
      (node (ref "M1") (pin "J1.12") (pinfunction "D9_J1.12") (pintype "bidirectional"))
    )
    (net (code "101") (name "P_4") (class "Default")
      (node (ref "ARDUINO_DUE1") (pin "4") (pinfunction "4_4") (pintype "bidirectional"))
      (node (ref "RA") (pin "7") (pinfunction "STEP_7") (pintype "input"))
    )
    (net (code "102") (name "P_5") (class "Default")
      (node (ref "ARDUINO_DUE1") (pin "5") (pinfunction "5_5") (pintype "bidirectional"))
      (node (ref "RA") (pin "8") (pinfunction "DIR_8") (pintype "input"))
    )
    (net (code "103") (name "P_6") (class "Default")
      (node (ref "ARDUINO_DUE1") (pin "6") (pinfunction "6_6") (pintype "bidirectional"))
      (node (ref "DEC") (pin "7") (pinfunction "STEP_7") (pintype "input"))
    )
    (net (code "104") (name "P_7") (class "Default")
      (node (ref "ARDUINO_DUE1") (pin "7") (pinfunction "7_7") (pintype "bidirectional"))
      (node (ref "DEC") (pin "8") (pinfunction "DIR_8") (pintype "input"))
    )
    (net (code "105") (name "P_14") (class "Default")
      (node (ref "ARDUINO_DUE1") (pin "14") (pinfunction "TX3_14_14") (pintype "bidirectional"))
      (node (ref "U$7") (pin "2") (pinfunction "RX_2") (pintype "bidirectional"))
    )
    (net (code "106") (name "P_15") (class "Default")
      (node (ref "ARDUINO_DUE1") (pin "15") (pinfunction "RX3_15_15") (pintype "bidirectional"))
      (node (ref "U$7") (pin "3") (pinfunction "TX_3") (pintype "bidirectional"))
    )
    (net (code "107") (name "P_16") (class "Default")
      (node (ref "ARDUINO_DUE1") (pin "16") (pinfunction "TX2_16_16") (pintype "bidirectional"))
      (node (ref "U$3") (pin "4") (pinfunction "RXD_4") (pintype "power_in"))
    )
    (net (code "108") (name "P_17") (class "Default")
      (node (ref "ARDUINO_DUE1") (pin "17") (pinfunction "RX2_17_17") (pintype "bidirectional"))
      (node (ref "U$3") (pin "3") (pinfunction "TXD_3") (pintype "bidirectional"))
    )
    (net (code "109") (name "P_18") (class "Default")
      (node (ref "ARDUINO_DUE1") (pin "18") (pinfunction "TX1_18_18") (pintype "bidirectional"))
      (node (ref "U$2") (pin "2") (pinfunction "RX_2") (pintype "bidirectional"))
    )
    (net (code "110") (name "P_19") (class "Default")
      (node (ref "ARDUINO_DUE1") (pin "19") (pinfunction "RX1_19_19") (pintype "bidirectional"))
      (node (ref "U$2") (pin "3") (pinfunction "TX_3") (pintype "bidirectional"))
    )
    (net (code "111") (name "P_21") (class "Default")
      (node (ref "ARDUINO_DUE1") (pin "21") (pinfunction "SCL_21_21") (pintype "bidirectional"))
      (node (ref "U$8") (pin "7") (pinfunction "CS_7") (pintype "bidirectional"))
      (node (ref "U1") (pin "CARD-CS") (pinfunction "CS-CARD_CARD-CS") (pintype "input"))
    )
    (net (code "112") (name "P_27") (class "Default")
      (node (ref "ARDUINO_DUE1") (pin "27") (pinfunction "27_27") (pintype "bidirectional"))
      (node (ref "FOCUS") (pin "8") (pinfunction "DIR_8") (pintype "input"))
    )
    (net (code "113") (name "P_29") (class "Default")
      (node (ref "ARDUINO_DUE1") (pin "29") (pinfunction "29_29") (pintype "bidirectional"))
      (node (ref "FOCUS") (pin "7") (pinfunction "STEP_7") (pintype "input"))
    )
    (net (code "114") (name "P_43") (class "Default")
      (node (ref "ARDUINO_DUE1") (pin "43") (pinfunction "43_43") (pintype "bidirectional"))
      (node (ref "R3") (pin "2") (pinfunction "2_2") (pintype "passive"))
      (node (ref "U$6") (pin "2") (pinfunction "DAT_2") (pintype "bidirectional"))
    )
    (net (code "115") (name "P_47") (class "Default")
      (node (ref "ARDUINO_DUE1") (pin "47") (pinfunction "47_47") (pintype "bidirectional"))
      (node (ref "RA") (pin "1") (pinfunction "~{EN}_1") (pintype "input"))
    )
    (net (code "116") (name "P_49") (class "Default")
      (node (ref "ARDUINO_DUE1") (pin "49") (pinfunction "49_49") (pintype "bidirectional"))
      (node (ref "DEC") (pin "1") (pinfunction "~{EN}_1") (pintype "input"))
    )
    (net (code "117") (name "P_51") (class "Default")
      (node (ref "ARDUINO_DUE1") (pin "51") (pinfunction "51_51") (pintype "bidirectional"))
      (node (ref "FOCUS") (pin "1") (pinfunction "~{EN}_1") (pintype "input"))
    )
    (net (code "118") (name "P_62") (class "Default")
      (node (ref "U$8") (pin "13") (pinfunction "MISO_13") (pintype "bidirectional"))
    )
    (net (code "119") (name "P_63") (class "Default")
      (node (ref "U$8") (pin "9") (pinfunction "MOSI_9") (pintype "bidirectional"))
    )
    (net (code "120") (name "P_64") (class "Default")
      (node (ref "U$8") (pin "11") (pinfunction "SCK_11") (pintype "bidirectional"))
    )
    (net (code "121") (name "P_A0") (class "Default")
      (node (ref "ARDUINO_DUE1") (pin "A0") (pinfunction "AN0_A0") (pintype "bidirectional"))
      (node (ref "R13") (pin "2") (pinfunction "2_2") (pintype "passive"))
      (node (ref "R14") (pin "1") (pinfunction "1_1") (pintype "passive"))
    )
    (net (code "122") (name "P_A1") (class "Default")
      (node (ref "ARDUINO_DUE1") (pin "A1") (pinfunction "AN1_A1") (pintype "bidirectional"))
      (node (ref "R11") (pin "2") (pinfunction "2_2") (pintype "passive"))
      (node (ref "R12") (pin "1") (pinfunction "1_1") (pintype "passive"))
    )
    (net (code "123") (name "P_A2") (class "Default")
      (node (ref "ARDUINO_DUE1") (pin "A2") (pinfunction "AN2_A2") (pintype "bidirectional"))
      (node (ref "C3") (pin "1") (pinfunction "1_1") (pintype "passive"))
      (node (ref "R4") (pin "1") (pinfunction "1_1") (pintype "passive"))
    )
    (net (code "124") (name "P_A3") (class "Default")
      (node (ref "ARDUINO_DUE1") (pin "A3") (pinfunction "AN3_A3") (pintype "bidirectional"))
      (node (ref "C4") (pin "1") (pinfunction "1_1") (pintype "passive"))
      (node (ref "R5") (pin "1") (pinfunction "1_1") (pintype "passive"))
    )
    (net (code "125") (name "P_A4") (class "Default")
      (node (ref "ARDUINO_DUE1") (pin "A4") (pinfunction "AN4_A4") (pintype "bidirectional"))
      (node (ref "U$5") (pin "J1.4") (pinfunction "SDA.1_J1.4") (pintype "bidirectional"))
    )
    (net (code "126") (name "P_A5") (class "Default")
      (node (ref "ARDUINO_DUE1") (pin "A5") (pinfunction "AN5_A5") (pintype "bidirectional"))
      (node (ref "U$5") (pin "J1.3") (pinfunction "SCL.1_J1.3") (pintype "bidirectional"))
    )
    (net (code "127") (name "P_A7") (class "Default")
      (node (ref "ARDUINO_DUE1") (pin "A7") (pinfunction "AN7_A7") (pintype "bidirectional"))
      (node (ref "R15") (pin "2") (pinfunction "2_2") (pintype "passive"))
      (node (ref "R16") (pin "1") (pinfunction "1_1") (pintype "passive"))
    )
    (net (code "128") (name "P_A9") (class "Default")
      (node (ref "ARDUINO_DUE1") (pin "A9") (pinfunction "AN9_A9") (pintype "bidirectional"))
      (node (ref "R17") (pin "1") (pinfunction "1_1") (pintype "passive"))
      (node (ref "R18") (pin "2") (pinfunction "2_2") (pintype "passive"))
    )
    (net (code "129") (name "RA+") (class "Default")
      (node (ref "M1") (pin "J1.7") (pinfunction "D4_J1.7") (pintype "bidirectional"))
      (node (ref "R6") (pin "1") (pinfunction "1_1") (pintype "passive"))
    )
    (net (code "130") (name "RA-") (class "Default")
      (node (ref "M1") (pin "J1.8") (pinfunction "D5_J1.8") (pintype "bidirectional"))
      (node (ref "R7") (pin "1") (pinfunction "1_1") (pintype "passive"))
    )
    (net (code "131") (name "RESET") (class "Default")
      (node (ref "ARDUINO_DUE1") (pin "RESET") (pinfunction "RESET_RESET") (pintype "bidirectional"))
      (node (ref "U1") (pin "RST") (pinfunction "~{RST}_RST") (pintype "input"))
    )
    (net (code "132") (name "SPK1") (class "Default")
      (node (ref "SV4") (pin "2") (pinfunction "S_2") (pintype "passive"))
      (node (ref "U$2") (pin "8") (pinfunction "SPK_2_8") (pintype "bidirectional"))
    )
    (net (code "133") (name "SPK2") (class "Default")
      (node (ref "SV4") (pin "1") (pinfunction "S_1") (pintype "passive"))
      (node (ref "U$2") (pin "6") (pinfunction "SPK_1_6") (pintype "bidirectional"))
    )
    (net (code "134") (name "SUP") (class "Default")
      (node (ref "ARDUINO_DUE1") (pin "GND") (pinfunction "GND_GND") (pintype "bidirectional"))
      (node (ref "ARDUINO_DUE1") (pin "GND_1") (pinfunction "GND_GND_1") (pintype "bidirectional"))
      (node (ref "ARDUINO_DUE1") (pin "GND_10") (pinfunction "GND_GND_10") (pintype "bidirectional"))
      (node (ref "ARDUINO_DUE1") (pin "GND_2") (pinfunction "GND_GND_2") (pintype "bidirectional"))
      (node (ref "ARDUINO_DUE1") (pin "GND_3") (pinfunction "GND_GND_3") (pintype "bidirectional"))
      (node (ref "ARDUINO_DUE1") (pin "GND_4") (pinfunction "GND_GND_4") (pintype "bidirectional"))
      (node (ref "ARDUINO_DUE1") (pin "GND_5") (pinfunction "GND_GND_5") (pintype "bidirectional"))
      (node (ref "ARDUINO_DUE1") (pin "GND_7") (pinfunction "GND_GND_7") (pintype "bidirectional"))
      (node (ref "ARDUINO_DUE1") (pin "GND_8") (pinfunction "GND_GND_8") (pintype "bidirectional"))
      (node (ref "ARDUINO_DUE1") (pin "GND_9") (pinfunction "GND_GND_9") (pintype "bidirectional"))
      (node (ref "C1") (pin "2") (pinfunction "2_2") (pintype "passive"))
      (node (ref "C2") (pin "2") (pinfunction "2_2") (pintype "passive"))
      (node (ref "C3") (pin "2") (pinfunction "2_2") (pintype "passive"))
      (node (ref "C4") (pin "2") (pinfunction "2_2") (pintype "passive"))
      (node (ref "C5") (pin "-") (pinfunction "-_-") (pintype "passive"))
      (node (ref "C6") (pin "-") (pinfunction "-_-") (pintype "passive"))
      (node (ref "C7") (pin "-") (pinfunction "-_-") (pintype "passive"))
      (node (ref "CN1") (pin "GND") (pinfunction "GND_GND") (pintype "power_in"))
      (node (ref "DEC") (pin "15") (pinfunction "GND_MOT_15") (pintype "power_in"))
      (node (ref "DEC") (pin "9") (pinfunction "GND_9") (pintype "power_in"))
      (node (ref "FOCUS") (pin "15") (pinfunction "GND_MOT_15") (pintype "power_in"))
      (node (ref "FOCUS") (pin "9") (pinfunction "GND_9") (pintype "power_in"))
      (node (ref "IC1") (pin "2") (pinfunction "GND_2") (pintype "passive"))
      (node (ref "M1") (pin "J1.4") (pinfunction "GND.1_J1.4") (pintype "power_in"))
      (node (ref "M1") (pin "J2.2") (pinfunction "GND.2_J2.2") (pintype "power_in"))
      (node (ref "OK1") (pin "2") (pinfunction "C_2") (pintype "passive"))
      (node (ref "OK2") (pin "2") (pinfunction "C_2") (pintype "passive"))
      (node (ref "OK3") (pin "2") (pinfunction "C_2") (pintype "passive"))
      (node (ref "OK4") (pin "2") (pinfunction "C_2") (pintype "passive"))
      (node (ref "OK5") (pin "2") (pinfunction "C_2") (pintype "passive"))
      (node (ref "R11") (pin "1") (pinfunction "1_1") (pintype "passive"))
      (node (ref "R13") (pin "1") (pinfunction "1_1") (pintype "passive"))
      (node (ref "R15") (pin "1") (pinfunction "1_1") (pintype "passive"))
      (node (ref "R18") (pin "1") (pinfunction "1_1") (pintype "passive"))
      (node (ref "RA") (pin "15") (pinfunction "GND_MOT_15") (pintype "power_in"))
      (node (ref "RA") (pin "9") (pinfunction "GND_9") (pintype "power_in"))
      (node (ref "T1") (pin "E") (pinfunction "E_E") (pintype "passive"))
      (node (ref "T2") (pin "E") (pinfunction "E_E") (pintype "passive"))
      (node (ref "T3") (pin "E") (pinfunction "E_E") (pintype "passive"))
      (node (ref "U$1") (pin "IN-") (pinfunction "IN-_IN-") (pintype "bidirectional"))
      (node (ref "U$1") (pin "OUT-") (pinfunction "OUT-_OUT-") (pintype "bidirectional"))
      (node (ref "U$2") (pin "10") (pinfunction "GND.2_10") (pintype "power_in"))
      (node (ref "U$2") (pin "7") (pinfunction "GND.1_7") (pintype "power_in"))
      (node (ref "U$3") (pin "2") (pinfunction "GND_2") (pintype "bidirectional"))
      (node (ref "U$4") (pin "1") (pinfunction "GND_1") (pintype "power_in"))
      (node (ref "U$5") (pin "J1.6") (pinfunction "GND.1_J1.6") (pintype "power_in"))
      (node (ref "U$5") (pin "J2.4") (pinfunction "GND.2_J2.4") (pintype "power_in"))
      (node (ref "U$6") (pin "4") (pinfunction "GND_4") (pintype "power_in"))
      (node (ref "U$7") (pin "4") (pinfunction "GND_4") (pintype "power_in"))
      (node (ref "U$8") (pin "1") (pinfunction "GND.1_1") (pintype "power_in"))
      (node (ref "U$8") (pin "15") (pinfunction "GND.2_15") (pintype "power_in"))
      (node (ref "U1") (pin "GND") (pinfunction "GND_GND") (pintype "power_in"))
      (node (ref "U1") (pin "GND3") (pinfunction "GND2_GND3") (pintype "power_in"))
    )
    (net (code "135") (name "unconnected-(ARDUINO_DUE1-5V_SPI-Pad5V_2)") (class "Default")
      (node (ref "ARDUINO_DUE1") (pin "5V_2") (pinfunction "5V_SPI_5V_2") (pintype "bidirectional"))
    )
    (net (code "136") (name "unconnected-(ARDUINO_DUE1-MASTER_R_JTAG-PadMASTER_RESET_JTAG)") (class "Default")
      (node (ref "ARDUINO_DUE1") (pin "MASTER_RESET_JTAG") (pinfunction "MASTER_R_JTAG_MASTER_RESET_JTAG") (pintype "bidirectional"))
    )
    (net (code "137") (name "unconnected-(ARDUINO_DUE1-MASTER_R_SPI-PadMASTER_RESET_SPI)") (class "Default")
      (node (ref "ARDUINO_DUE1") (pin "MASTER_RESET_SPI") (pinfunction "MASTER_R_SPI_MASTER_RESET_SPI") (pintype "bidirectional"))
    )
    (net (code "138") (name "unconnected-(ARDUINO_DUE1-NC-PadNC_2)") (class "Default")
      (node (ref "ARDUINO_DUE1") (pin "NC_2") (pinfunction "NC_NC_2") (pintype "no_connect"))
    )
    (net (code "139") (name "unconnected-(ARDUINO_DUE1-NC-PadNC_5)") (class "Default")
      (node (ref "ARDUINO_DUE1") (pin "NC_5") (pinfunction "NC_NC_5") (pintype "bidirectional"))
    )
    (net (code "140") (name "unconnected-(ARDUINO_DUE1-Pad3V3_JTAG)") (class "Default")
      (node (ref "ARDUINO_DUE1") (pin "3V3_JTAG") (pinfunction "3V3_JTAG_3V3_JTAG") (pintype "bidirectional"))
    )
    (net (code "141") (name "unconnected-(ARDUINO_DUE1-Pad5V_ICSP1)") (class "Default")
      (node (ref "ARDUINO_DUE1") (pin "5V_ICSP1") (pinfunction "5V_ICSP1_5V_ICSP1") (pintype "bidirectional"))
    )
    (net (code "142") (name "unconnected-(ARDUINO_DUE1-PadAREF)") (class "Default")
      (node (ref "ARDUINO_DUE1") (pin "AREF") (pinfunction "AREF_AREF") (pintype "bidirectional"))
    )
    (net (code "143") (name "unconnected-(ARDUINO_DUE1-PadGND_ICSP1)") (class "Default")
      (node (ref "ARDUINO_DUE1") (pin "GND_ICSP1") (pinfunction "GND_ICSP1_GND_ICSP1") (pintype "bidirectional"))
    )
    (net (code "144") (name "unconnected-(ARDUINO_DUE1-PadIOREF)") (class "Default")
      (node (ref "ARDUINO_DUE1") (pin "IOREF") (pinfunction "IOREF_IOREF") (pintype "bidirectional"))
    )
    (net (code "145") (name "unconnected-(ARDUINO_DUE1-PadJTAG_RESET)") (class "Default")
      (node (ref "ARDUINO_DUE1") (pin "JTAG_RESET") (pinfunction "JTAG_RESET_JTAG_RESET") (pintype "bidirectional"))
    )
    (net (code "146") (name "unconnected-(ARDUINO_DUE1-PadJTAG_TCK)") (class "Default")
      (node (ref "ARDUINO_DUE1") (pin "JTAG_TCK") (pinfunction "JTAG_TCK_JTAG_TCK") (pintype "bidirectional"))
    )
    (net (code "147") (name "unconnected-(ARDUINO_DUE1-PadJTAG_TCK_2)") (class "Default")
      (node (ref "ARDUINO_DUE1") (pin "JTAG_TCK_2") (pinfunction "JTAG_TCK_2_JTAG_TCK_2") (pintype "bidirectional"))
    )
    (net (code "148") (name "unconnected-(ARDUINO_DUE1-PadJTAG_TDI)") (class "Default")
      (node (ref "ARDUINO_DUE1") (pin "JTAG_TDI") (pinfunction "JTAG_TDI_JTAG_TDI") (pintype "bidirectional"))
    )
    (net (code "149") (name "unconnected-(ARDUINO_DUE1-PadJTAG_TDO)") (class "Default")
      (node (ref "ARDUINO_DUE1") (pin "JTAG_TDO") (pinfunction "JTAG_TDO_JTAG_TDO") (pintype "bidirectional"))
    )
    (net (code "150") (name "unconnected-(ARDUINO_DUE1-PadJTAG_TMS)") (class "Default")
      (node (ref "ARDUINO_DUE1") (pin "JTAG_TMS") (pinfunction "JTAG_TMS_JTAG_TMS") (pintype "bidirectional"))
    )
    (net (code "151") (name "unconnected-(ARDUINO_DUE1-PadJTAG_TMS_2)") (class "Default")
      (node (ref "ARDUINO_DUE1") (pin "JTAG_TMS_2") (pinfunction "JTAG_TMS_2_JTAG_TMS_2") (pintype "bidirectional"))
    )
    (net (code "152") (name "unconnected-(ARDUINO_DUE1-PadMISO2)") (class "Default")
      (node (ref "ARDUINO_DUE1") (pin "MISO2") (pinfunction "MISO2_MISO2") (pintype "bidirectional"))
    )
    (net (code "153") (name "unconnected-(ARDUINO_DUE1-PadMOSI2)") (class "Default")
      (node (ref "ARDUINO_DUE1") (pin "MOSI2") (pinfunction "MOSI2_MOSI2") (pintype "bidirectional"))
    )
    (net (code "154") (name "unconnected-(ARDUINO_DUE1-PadRESET2)") (class "Default")
      (node (ref "ARDUINO_DUE1") (pin "RESET2") (pinfunction "RESET2_RESET2") (pintype "bidirectional"))
    )
    (net (code "155") (name "unconnected-(ARDUINO_DUE1-PadSCK2)") (class "Default")
      (node (ref "ARDUINO_DUE1") (pin "SCK2") (pinfunction "SCK2_SCK2") (pintype "bidirectional"))
    )
    (net (code "156") (name "unconnected-(ARDUINO_DUE1-PadSCL1)") (class "Default")
      (node (ref "ARDUINO_DUE1") (pin "SCL1") (pinfunction "SCL1_SCL1") (pintype "bidirectional"))
    )
    (net (code "157") (name "unconnected-(ARDUINO_DUE1-PadSDA1)") (class "Default")
      (node (ref "ARDUINO_DUE1") (pin "SDA1") (pinfunction "SDA1_SDA1") (pintype "bidirectional"))
    )
    (net (code "158") (name "unconnected-(EN1-PadA)") (class "Default")
      (node (ref "EN1") (pin "A") (pinfunction "A_A") (pintype "passive"))
    )
    (net (code "159") (name "unconnected-(EN1-PadB)") (class "Default")
      (node (ref "EN1") (pin "B") (pinfunction "B_B") (pintype "passive"))
    )
    (net (code "160") (name "unconnected-(EN1-PadB1)") (class "Default")
      (node (ref "EN1") (pin "B1") (pinfunction "B1_B1") (pintype "passive"))
    )
    (net (code "161") (name "unconnected-(EN1-PadCOM)") (class "Default")
      (node (ref "EN1") (pin "COM") (pinfunction "COM_COM") (pintype "passive"))
    )
    (net (code "162") (name "unconnected-(EN1-PadS)") (class "Default")
      (node (ref "EN1") (pin "S") (pinfunction "S_S") (pintype "passive"))
    )
    (net (code "163") (name "unconnected-(M1-A0-PadJ2.12)") (class "Default")
      (node (ref "M1") (pin "J2.12") (pinfunction "A0_J2.12") (pintype "bidirectional"))
    )
    (net (code "164") (name "unconnected-(M1-A1-PadJ2.11)") (class "Default")
      (node (ref "M1") (pin "J2.11") (pinfunction "A1_J2.11") (pintype "bidirectional"))
    )
    (net (code "165") (name "unconnected-(M1-A2-PadJ2.10)") (class "Default")
      (node (ref "M1") (pin "J2.10") (pinfunction "A2_J2.10") (pintype "bidirectional"))
    )
    (net (code "166") (name "unconnected-(M1-A3-PadJ2.9)") (class "Default")
      (node (ref "M1") (pin "J2.9") (pinfunction "A3_J2.9") (pintype "bidirectional"))
    )
    (net (code "167") (name "unconnected-(M1-A4-PadJ2.8)") (class "Default")
      (node (ref "M1") (pin "J2.8") (pinfunction "A4_J2.8") (pintype "bidirectional"))
    )
    (net (code "168") (name "unconnected-(M1-A5-PadJ2.7)") (class "Default")
      (node (ref "M1") (pin "J2.7") (pinfunction "A5_J2.7") (pintype "bidirectional"))
    )
    (net (code "169") (name "unconnected-(M1-A6-PadJ2.6)") (class "Default")
      (node (ref "M1") (pin "J2.6") (pinfunction "A6_J2.6") (pintype "bidirectional"))
    )
    (net (code "170") (name "unconnected-(M1-A7-PadJ2.5)") (class "Default")
      (node (ref "M1") (pin "J2.5") (pinfunction "A7_J2.5") (pintype "bidirectional"))
    )
    (net (code "171") (name "unconnected-(M1-AREF-PadJ2.13)") (class "Default")
      (node (ref "M1") (pin "J2.13") (pinfunction "AREF_J2.13") (pintype "bidirectional"))
    )
    (net (code "172") (name "unconnected-(M1-D0{slash}RX-PadJ1.2)") (class "Default")
      (node (ref "M1") (pin "J1.2") (pinfunction "D0/RX_J1.2") (pintype "bidirectional"))
    )
    (net (code "173") (name "unconnected-(M1-D1{slash}TX-PadJ1.1)") (class "Default")
      (node (ref "M1") (pin "J1.1") (pinfunction "D1/TX_J1.1") (pintype "bidirectional"))
    )
    (net (code "174") (name "unconnected-(M1-D2-PadJ1.5)") (class "Default")
      (node (ref "M1") (pin "J1.5") (pinfunction "D2_J1.5") (pintype "bidirectional"))
    )
    (net (code "175") (name "unconnected-(M1-D10-PadJ1.13)") (class "Default")
      (node (ref "M1") (pin "J1.13") (pinfunction "D10_J1.13") (pintype "bidirectional"))
    )
    (net (code "176") (name "unconnected-(M1-D11{slash}MOSI-PadJ1.14)") (class "Default")
      (node (ref "M1") (pin "J1.14") (pinfunction "D11/MOSI_J1.14") (pintype "bidirectional"))
    )
    (net (code "177") (name "unconnected-(M1-D12{slash}MISO-PadJ1.15)") (class "Default")
      (node (ref "M1") (pin "J1.15") (pinfunction "D12/MISO_J1.15") (pintype "bidirectional"))
    )
    (net (code "178") (name "unconnected-(M1-D13{slash}SCK-PadJ2.15)") (class "Default")
      (node (ref "M1") (pin "J2.15") (pinfunction "D13/SCK_J2.15") (pintype "bidirectional"))
    )
    (net (code "179") (name "unconnected-(M1-RST.1-PadJ1.3)") (class "Default")
      (node (ref "M1") (pin "J1.3") (pinfunction "RST.1_J1.3") (pintype "bidirectional"))
    )
    (net (code "180") (name "unconnected-(M1-RST.2-PadJ2.3)") (class "Default")
      (node (ref "M1") (pin "J2.3") (pinfunction "RST.2_J2.3") (pintype "bidirectional"))
    )
    (net (code "181") (name "unconnected-(R19-Pad1)") (class "Default")
      (node (ref "R19") (pin "1") (pinfunction "1_1") (pintype "passive"))
    )
    (net (code "182") (name "unconnected-(R20-Pad1)") (class "Default")
      (node (ref "R20") (pin "1") (pinfunction "1_1") (pintype "passive"))
    )
    (net (code "183") (name "unconnected-(R21-Pad1)") (class "Default")
      (node (ref "R21") (pin "1") (pinfunction "1_1") (pintype "passive"))
    )
    (net (code "184") (name "unconnected-(R22-Pad1)") (class "Default")
      (node (ref "R22") (pin "1") (pinfunction "1_1") (pintype "passive"))
    )
    (net (code "185") (name "unconnected-(R23-Pad1)") (class "Default")
      (node (ref "R23") (pin "1") (pinfunction "1_1") (pintype "passive"))
    )
    (net (code "186") (name "unconnected-(U$2-ADKEY_1-Pad12)") (class "Default")
      (node (ref "U$2") (pin "12") (pinfunction "ADKEY_1_12") (pintype "bidirectional"))
    )
    (net (code "187") (name "unconnected-(U$2-ADKEY_2-Pad13)") (class "Default")
      (node (ref "U$2") (pin "13") (pinfunction "ADKEY_2_13") (pintype "bidirectional"))
    )
    (net (code "188") (name "unconnected-(U$2-BUSY-Pad16)") (class "Default")
      (node (ref "U$2") (pin "16") (pinfunction "BUSY_16") (pintype "bidirectional"))
    )
    (net (code "189") (name "unconnected-(U$2-DAC_I-Pad5)") (class "Default")
      (node (ref "U$2") (pin "5") (pinfunction "DAC_I_5") (pintype "bidirectional"))
    )
    (net (code "190") (name "unconnected-(U$2-DAC_R-Pad4)") (class "Default")
      (node (ref "U$2") (pin "4") (pinfunction "DAC_R_4") (pintype "bidirectional"))
    )
    (net (code "191") (name "unconnected-(U$2-IO_1-Pad9)") (class "Default")
      (node (ref "U$2") (pin "9") (pinfunction "IO_1_9") (pintype "bidirectional"))
    )
    (net (code "192") (name "unconnected-(U$2-IO_2-Pad11)") (class "Default")
      (node (ref "U$2") (pin "11") (pinfunction "IO_2_11") (pintype "bidirectional"))
    )
    (net (code "193") (name "unconnected-(U$2-USB+-Pad14)") (class "Default")
      (node (ref "U$2") (pin "14") (pinfunction "USB+_14") (pintype "bidirectional"))
    )
    (net (code "194") (name "unconnected-(U$2-USB--Pad15)") (class "Default")
      (node (ref "U$2") (pin "15") (pinfunction "USB-_15") (pintype "bidirectional"))
    )
    (net (code "195") (name "unconnected-(U$5-32K-PadJ1.1)") (class "Default")
      (node (ref "U$5") (pin "J1.1") (pinfunction "32K_J1.1") (pintype "bidirectional"))
    )
    (net (code "196") (name "unconnected-(U$5-SCL.2-PadJ2.1)") (class "Default")
      (node (ref "U$5") (pin "J2.1") (pinfunction "SCL.2_J2.1") (pintype "bidirectional"))
    )
    (net (code "197") (name "unconnected-(U$5-SDA.2-PadJ2.2)") (class "Default")
      (node (ref "U$5") (pin "J2.2") (pinfunction "SDA.2_J2.2") (pintype "bidirectional"))
    )
    (net (code "198") (name "unconnected-(U$5-SQW-PadJ1.2)") (class "Default")
      (node (ref "U$5") (pin "J1.2") (pinfunction "SQW_J1.2") (pintype "bidirectional"))
    )
    (net (code "199") (name "unconnected-(U$6-N.C.-Pad3)") (class "Default")
      (node (ref "U$6") (pin "3") (pinfunction "N.C._3") (pintype "passive"))
    )
    (net (code "200") (name "unconnected-(U$7-EN-Pad6)") (class "Default")
      (node (ref "U$7") (pin "6") (pinfunction "EN_6") (pintype "bidirectional"))
    )
    (net (code "201") (name "unconnected-(U$7-STATE-Pad1)") (class "Default")
      (node (ref "U$7") (pin "1") (pinfunction "STATE_1") (pintype "bidirectional"))
    )
  )
)
